# PHAS-Hub.net
KiCad netlist of a schematic drawn in EAGLE
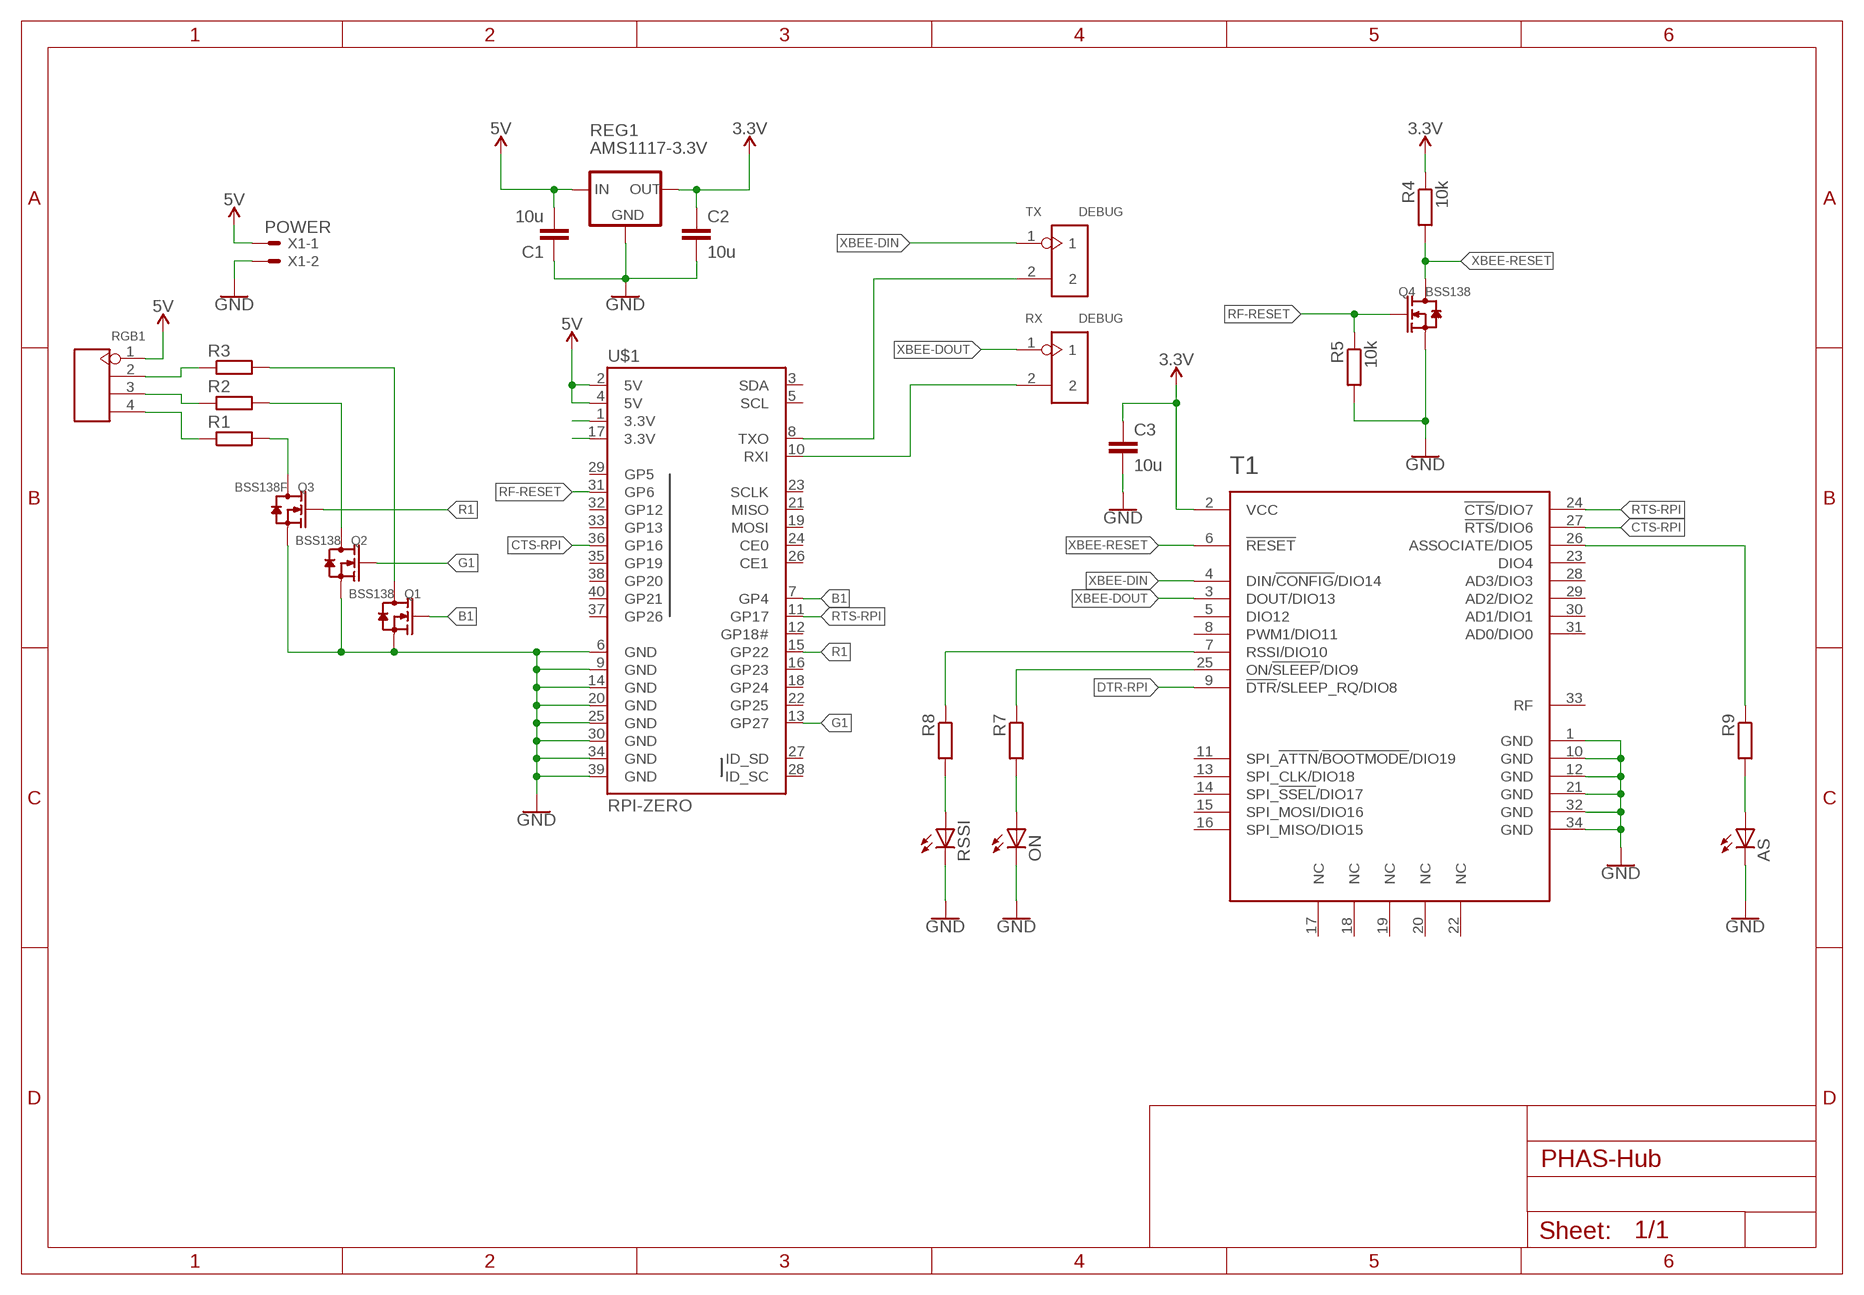
[diagram p0: schematic, sheet 1]

(export (version "E")
  (design (tool "Eeschema 10.0.6"))
  (components
    (comp (ref "AS")
      (value "LEDCHIPLED_0805")
      (footprint "eagle-import:CHIPLED_0805")
      (libsource (lib "eagle-import") (part "LEDCHIPLED_0805"))
    )
    (comp (ref "C1")
      (value "10u")
      (footprint "eagle-import:C0805")
      (libsource (lib "eagle-import") (part "C-EUC0805"))
    )
    (comp (ref "C2")
      (value "10u")
      (footprint "eagle-import:C0805")
      (libsource (lib "eagle-import") (part "C-EUC0805"))
    )
    (comp (ref "C3")
      (value "10u")
      (footprint "eagle-import:C0805")
      (libsource (lib "eagle-import") (part "C-EUC0805"))
    )
    (comp (ref "ON")
      (value "LEDCHIPLED_0805")
      (footprint "eagle-import:CHIPLED_0805")
      (libsource (lib "eagle-import") (part "LEDCHIPLED_0805"))
    )
    (comp (ref "Q1")
      (value "BSS138")
      (footprint "eagle-import:SOT-23")
      (fields (field (name "MPN") "BSS138W-7-F"))
      (libsource (lib "eagle-import") (part "SMD-MOSFET-N-CH-50V-200MA-BSS138W-7-F(SOT-23)"))
    )
    (comp (ref "Q2")
      (value "BSS138")
      (footprint "eagle-import:SOT-23")
      (fields (field (name "MPN") "BSS138W-7-F"))
      (libsource (lib "eagle-import") (part "SMD-MOSFET-N-CH-50V-200MA-BSS138W-7-F(SOT-23)"))
    )
    (comp (ref "Q3")
      (value "BSS138F")
      (footprint "eagle-import:SOT-23")
      (fields (field (name "MPN") "BSS138W-7-F"))
      (libsource (lib "eagle-import") (part "SMD-MOSFET-N-CH-50V-200MA-BSS138W-7-F(SOT-23)"))
    )
    (comp (ref "Q4")
      (value "BSS138")
      (footprint "eagle-import:SOT-23")
      (fields (field (name "MPN") "BSS138W-7-F"))
      (libsource (lib "eagle-import") (part "SMD-MOSFET-N-CH-50V-200MA-BSS138W-7-F(SOT-23)"))
    )
    (comp (ref "R1")
      (value "R-EU_R0805")
      (footprint "eagle-import:R0805")
      (libsource (lib "eagle-import") (part "R-EU_R0805"))
    )
    (comp (ref "R2")
      (value "R-EU_R0805")
      (footprint "eagle-import:R0805")
      (libsource (lib "eagle-import") (part "R-EU_R0805"))
    )
    (comp (ref "R3")
      (value "R-EU_R0805")
      (footprint "eagle-import:R0805")
      (libsource (lib "eagle-import") (part "R-EU_R0805"))
    )
    (comp (ref "R4")
      (value "10k")
      (footprint "eagle-import:R0805")
      (libsource (lib "eagle-import") (part "R-EU_R0805"))
    )
    (comp (ref "R5")
      (value "10k")
      (footprint "eagle-import:R0805")
      (libsource (lib "eagle-import") (part "R-EU_R0805"))
    )
    (comp (ref "R7")
      (value "R-EU_R0805")
      (footprint "eagle-import:R0805")
      (libsource (lib "eagle-import") (part "R-EU_R0805"))
    )
    (comp (ref "R8")
      (value "R-EU_R0805")
      (footprint "eagle-import:R0805")
      (libsource (lib "eagle-import") (part "R-EU_R0805"))
    )
    (comp (ref "R9")
      (value "R-EU_R0805")
      (footprint "eagle-import:R0805")
      (libsource (lib "eagle-import") (part "R-EU_R0805"))
    )
    (comp (ref "REG1")
      (value "AMS1117-3.3V")
      (footprint "eagle-import:SOT223")
      (fields (field (name "MF") "Texas Instruments") (field (name "MPN") "LM1117MP-3.3"))
      (libsource (lib "eagle-import") (part "LM1117?-MP3.3"))
    )
    (comp (ref "RGB1")
      (value "DIP-BLACK-MALE-HEADER-VERT(4P-2.54)")
      (footprint "eagle-import:H4-2.54")
      (fields (field (name "MPN") "P125-1104A0BS116A1"))
      (libsource (lib "eagle-import") (part "DIP-BLACK-MALE-HEADER-VERT(4P-2.54)"))
    )
    (comp (ref "RSSI")
      (value "LEDCHIPLED_0805")
      (footprint "eagle-import:CHIPLED_0805")
      (libsource (lib "eagle-import") (part "LEDCHIPLED_0805"))
    )
    (comp (ref "RX")
      (value "DEBUG")
      (footprint "eagle-import:H2-2.54")
      (fields (field (name "MPN") "P125-1102A0BS116A1"))
      (libsource (lib "eagle-import") (part "DIP-BLACK-MALE-HEADER-VERT(2P-2.54)"))
    )
    (comp (ref "T1")
      (value "XBEE3-MICRO")
      (footprint "eagle-import:XBEE3-MICRO")
      (libsource (lib "eagle-import") (part "XBEE3-MICRO"))
    )
    (comp (ref "TX")
      (value "DEBUG")
      (footprint "eagle-import:H2-2.54")
      (fields (field (name "MPN") "P125-1102A0BS116A1"))
      (libsource (lib "eagle-import") (part "DIP-BLACK-MALE-HEADER-VERT(2P-2.54)"))
    )
    (comp (ref "U$1")
      (value "RPI-ZERO")
      (footprint "eagle-import:RASPBERRYPI_BASTELSTUBE_V13_RASPI_BOARD_B+_FULL")
      (libsource (lib "eagle-import") (part "RPI-ZERO"))
    )
    (comp (ref "X1")
      (value "POWER")
      (footprint "eagle-import:70543-02")
      (fields (field (name "MF") "MOLEX"))
      (libsource (lib "eagle-import") (part "C-GRID-02-70543"))
    )
  )
  (nets
    (net (code "1") (name "3.3V") (class "Default")
      (node (ref "C2") (pin "1") (pinfunction "1_1") (pintype "passive"))
      (node (ref "C3") (pin "1") (pinfunction "1_1") (pintype "passive"))
      (node (ref "R4") (pin "1") (pinfunction "1_1") (pintype "passive"))
      (node (ref "REG1") (pin "2") (pinfunction "OUT_2") (pintype "passive"))
      (node (ref "REG1") (pin "4") (pinfunction "OUT_4") (pintype "passive"))
      (node (ref "T1") (pin "2") (pinfunction "VCC_2") (pintype "power_in"))
    )
    (net (code "2") (name "5V") (class "Default")
      (node (ref "C1") (pin "2") (pinfunction "2_2") (pintype "passive"))
      (node (ref "REG1") (pin "3") (pinfunction "IN_3") (pintype "input"))
      (node (ref "RGB1") (pin "1") (pinfunction "P$1_1") (pintype "bidirectional"))
      (node (ref "U$1") (pin "2") (pinfunction "5V_2") (pintype "power_in"))
      (node (ref "U$1") (pin "4") (pinfunction "5V_4") (pintype "power_in"))
      (node (ref "X1") (pin "1") (pinfunction "S_1") (pintype "passive"))
    )
    (net (code "3") (name "B1") (class "Default")
      (node (ref "Q1") (pin "1") (pinfunction "G_1") (pintype "passive"))
      (node (ref "U$1") (pin "7") (pinfunction "GP4_7") (pintype "bidirectional"))
    )
    (net (code "4") (name "CTS-RPI") (class "Default")
      (node (ref "T1") (pin "27") (pinfunction "~{RTS}/DIO6_27") (pintype "bidirectional"))
      (node (ref "U$1") (pin "36") (pinfunction "GP16_36") (pintype "bidirectional"))
    )
    (net (code "5") (name "DTR-RPI") (class "Default")
      (node (ref "T1") (pin "9") (pinfunction "~{DTR}/SLEEP_RQ/DIO8_9") (pintype "bidirectional"))
    )
    (net (code "6") (name "G1") (class "Default")
      (node (ref "Q2") (pin "1") (pinfunction "G_1") (pintype "passive"))
      (node (ref "U$1") (pin "13") (pinfunction "GP27_13") (pintype "bidirectional"))
    )
    (net (code "7") (name "GND") (class "Default")
      (node (ref "AS") (pin "C") (pinfunction "C_C") (pintype "passive"))
      (node (ref "C1") (pin "1") (pinfunction "1_1") (pintype "passive"))
      (node (ref "C2") (pin "2") (pinfunction "2_2") (pintype "passive"))
      (node (ref "C3") (pin "2") (pinfunction "2_2") (pintype "passive"))
      (node (ref "ON") (pin "C") (pinfunction "C_C") (pintype "passive"))
      (node (ref "Q1") (pin "2") (pinfunction "S_2") (pintype "passive"))
      (node (ref "Q2") (pin "2") (pinfunction "S_2") (pintype "passive"))
      (node (ref "Q3") (pin "2") (pinfunction "S_2") (pintype "passive"))
      (node (ref "Q4") (pin "2") (pinfunction "S_2") (pintype "passive"))
      (node (ref "R5") (pin "2") (pinfunction "2_2") (pintype "passive"))
      (node (ref "REG1") (pin "1") (pinfunction "GND_1") (pintype "input"))
      (node (ref "RSSI") (pin "C") (pinfunction "C_C") (pintype "passive"))
      (node (ref "T1") (pin "1") (pinfunction "GND_1") (pintype "power_in"))
      (node (ref "T1") (pin "10") (pinfunction "GND_10") (pintype "power_in"))
      (node (ref "T1") (pin "12") (pinfunction "GND_12") (pintype "power_in"))
      (node (ref "T1") (pin "21") (pinfunction "GND_21") (pintype "power_in"))
      (node (ref "T1") (pin "32") (pinfunction "GND_32") (pintype "power_in"))
      (node (ref "T1") (pin "34") (pinfunction "GND_34") (pintype "power_in"))
      (node (ref "U$1") (pin "14") (pinfunction "GND_14") (pintype "power_in"))
      (node (ref "U$1") (pin "20") (pinfunction "GND_20") (pintype "power_in"))
      (node (ref "U$1") (pin "25") (pinfunction "GND_25") (pintype "power_in"))
      (node (ref "U$1") (pin "30") (pinfunction "GND_30") (pintype "power_in"))
      (node (ref "U$1") (pin "34") (pinfunction "GND_34") (pintype "power_in"))
      (node (ref "U$1") (pin "39") (pinfunction "GND_39") (pintype "power_in"))
      (node (ref "U$1") (pin "6") (pinfunction "GND_6") (pintype "power_in"))
      (node (ref "U$1") (pin "9") (pinfunction "GND_9") (pintype "power_in"))
      (node (ref "X1") (pin "2") (pinfunction "S_2") (pintype "passive"))
    )
    (net (code "8") (name "Net-(AS-PadA)") (class "Default")
      (node (ref "AS") (pin "A") (pinfunction "A_A") (pintype "passive"))
      (node (ref "R9") (pin "2") (pinfunction "2_2") (pintype "passive"))
    )
    (net (code "9") (name "Net-(ON-PadA)") (class "Default")
      (node (ref "ON") (pin "A") (pinfunction "A_A") (pintype "passive"))
      (node (ref "R7") (pin "2") (pinfunction "2_2") (pintype "passive"))
    )
    (net (code "10") (name "Net-(Q1-D)") (class "Default")
      (node (ref "Q1") (pin "3") (pinfunction "D_3") (pintype "passive"))
      (node (ref "R3") (pin "2") (pinfunction "2_2") (pintype "passive"))
    )
    (net (code "11") (name "Net-(Q2-D)") (class "Default")
      (node (ref "Q2") (pin "3") (pinfunction "D_3") (pintype "passive"))
      (node (ref "R2") (pin "2") (pinfunction "2_2") (pintype "passive"))
    )
    (net (code "12") (name "Net-(Q3-D)") (class "Default")
      (node (ref "Q3") (pin "3") (pinfunction "D_3") (pintype "passive"))
      (node (ref "R1") (pin "2") (pinfunction "2_2") (pintype "passive"))
    )
    (net (code "13") (name "Net-(R8-Pad2)") (class "Default")
      (node (ref "R8") (pin "2") (pinfunction "2_2") (pintype "passive"))
      (node (ref "RSSI") (pin "A") (pinfunction "A_A") (pintype "passive"))
    )
    (net (code "14") (name "Net-(RGB1-P$2)") (class "Default")
      (node (ref "R3") (pin "1") (pinfunction "1_1") (pintype "passive"))
      (node (ref "RGB1") (pin "2") (pinfunction "P$2_2") (pintype "bidirectional"))
    )
    (net (code "15") (name "Net-(RGB1-P$3)") (class "Default")
      (node (ref "R2") (pin "1") (pinfunction "1_1") (pintype "passive"))
      (node (ref "RGB1") (pin "3") (pinfunction "P$3_3") (pintype "bidirectional"))
    )
    (net (code "16") (name "Net-(RGB1-P$4)") (class "Default")
      (node (ref "R1") (pin "1") (pinfunction "1_1") (pintype "passive"))
      (node (ref "RGB1") (pin "4") (pinfunction "P$4_4") (pintype "bidirectional"))
    )
    (net (code "17") (name "Net-(T1-ASSOCIATE{slash}DIO5)") (class "Default")
      (node (ref "R9") (pin "1") (pinfunction "1_1") (pintype "passive"))
      (node (ref "T1") (pin "26") (pinfunction "ASSOCIATE/DIO5_26") (pintype "bidirectional"))
    )
    (net (code "18") (name "Net-(T1-ON{slash}~{SLEEP}{slash}DIO9)") (class "Default")
      (node (ref "R7") (pin "1") (pinfunction "1_1") (pintype "passive"))
      (node (ref "T1") (pin "25") (pinfunction "ON/~{SLEEP}/DIO9_25") (pintype "bidirectional"))
    )
    (net (code "19") (name "Net-(T1-RSSI{slash}DIO10)") (class "Default")
      (node (ref "R8") (pin "1") (pinfunction "1_1") (pintype "passive"))
      (node (ref "T1") (pin "7") (pinfunction "RSSI/DIO10_7") (pintype "bidirectional"))
    )
    (net (code "20") (name "Net-(U$1-RXI)") (class "Default")
      (node (ref "RX") (pin "2") (pinfunction "2_2") (pintype "bidirectional"))
      (node (ref "U$1") (pin "10") (pinfunction "RXI_10") (pintype "input"))
    )
    (net (code "21") (name "Net-(U$1-TXO)") (class "Default")
      (node (ref "TX") (pin "2") (pinfunction "2_2") (pintype "bidirectional"))
      (node (ref "U$1") (pin "8") (pinfunction "TXO_8") (pintype "output"))
    )
    (net (code "22") (name "R1") (class "Default")
      (node (ref "Q3") (pin "1") (pinfunction "G_1") (pintype "passive"))
      (node (ref "U$1") (pin "15") (pinfunction "GP22_15") (pintype "bidirectional"))
    )
    (net (code "23") (name "RF-RESET") (class "Default")
      (node (ref "Q4") (pin "1") (pinfunction "G_1") (pintype "passive"))
      (node (ref "R5") (pin "1") (pinfunction "1_1") (pintype "passive"))
      (node (ref "U$1") (pin "31") (pinfunction "GP6_31") (pintype "bidirectional"))
    )
    (net (code "24") (name "RTS-RPI") (class "Default")
      (node (ref "T1") (pin "24") (pinfunction "~{CTS}/DIO7_24") (pintype "bidirectional"))
      (node (ref "U$1") (pin "11") (pinfunction "GP17_11") (pintype "bidirectional"))
    )
    (net (code "25") (name "XBEE-DIN") (class "Default")
      (node (ref "T1") (pin "4") (pinfunction "DIN/~{CONFIG}/DIO14_4") (pintype "bidirectional"))
      (node (ref "TX") (pin "1") (pinfunction "1_1") (pintype "bidirectional"))
    )
    (net (code "26") (name "XBEE-DOUT") (class "Default")
      (node (ref "RX") (pin "1") (pinfunction "1_1") (pintype "bidirectional"))
      (node (ref "T1") (pin "3") (pinfunction "DOUT/DIO13_3") (pintype "bidirectional"))
    )
    (net (code "27") (name "XBEE-RESET") (class "Default")
      (node (ref "Q4") (pin "3") (pinfunction "D_3") (pintype "passive"))
      (node (ref "R4") (pin "2") (pinfunction "2_2") (pintype "passive"))
      (node (ref "T1") (pin "6") (pinfunction "~{RESET}_6") (pintype "input"))
    )
    (net (code "28") (name "unconnected-(T1-AD0{slash}DIO0-Pad31)") (class "Default")
      (node (ref "T1") (pin "31") (pinfunction "AD0/DIO0_31") (pintype "bidirectional"))
    )
    (net (code "29") (name "unconnected-(T1-AD1{slash}DIO1-Pad30)") (class "Default")
      (node (ref "T1") (pin "30") (pinfunction "AD1/DIO1_30") (pintype "bidirectional"))
    )
    (net (code "30") (name "unconnected-(T1-AD2{slash}DIO2-Pad29)") (class "Default")
      (node (ref "T1") (pin "29") (pinfunction "AD2/DIO2_29") (pintype "bidirectional"))
    )
    (net (code "31") (name "unconnected-(T1-AD3{slash}DIO3-Pad28)") (class "Default")
      (node (ref "T1") (pin "28") (pinfunction "AD3/DIO3_28") (pintype "bidirectional"))
    )
    (net (code "32") (name "unconnected-(T1-DIO4-Pad23)") (class "Default")
      (node (ref "T1") (pin "23") (pinfunction "DIO4_23") (pintype "bidirectional"))
    )
    (net (code "33") (name "unconnected-(T1-DIO12-Pad5)") (class "Default")
      (node (ref "T1") (pin "5") (pinfunction "DIO12_5") (pintype "bidirectional"))
    )
    (net (code "34") (name "unconnected-(T1-NC-Pad17)") (class "Default")
      (node (ref "T1") (pin "17") (pinfunction "NC_17") (pintype "bidirectional"))
    )
    (net (code "35") (name "unconnected-(T1-NC-Pad18)") (class "Default")
      (node (ref "T1") (pin "18") (pinfunction "NC_18") (pintype "bidirectional"))
    )
    (net (code "36") (name "unconnected-(T1-NC-Pad19)") (class "Default")
      (node (ref "T1") (pin "19") (pinfunction "NC_19") (pintype "bidirectional"))
    )
    (net (code "37") (name "unconnected-(T1-NC-Pad20)") (class "Default")
      (node (ref "T1") (pin "20") (pinfunction "NC_20") (pintype "bidirectional"))
    )
    (net (code "38") (name "unconnected-(T1-NC-Pad22)") (class "Default")
      (node (ref "T1") (pin "22") (pinfunction "NC_22") (pintype "bidirectional"))
    )
    (net (code "39") (name "unconnected-(T1-PWM1{slash}DIO11-Pad8)") (class "Default")
      (node (ref "T1") (pin "8") (pinfunction "PWM1/DIO11_8") (pintype "bidirectional"))
    )
    (net (code "40") (name "unconnected-(T1-RF-Pad33)") (class "Default")
      (node (ref "T1") (pin "33") (pinfunction "RF_33") (pintype "output"))
    )
    (net (code "41") (name "unconnected-(T1-SPI_CLK{slash}DIO18-Pad13)") (class "Default")
      (node (ref "T1") (pin "13") (pinfunction "SPI_CLK/DIO18_13") (pintype "bidirectional"))
    )
    (net (code "42") (name "unconnected-(T1-SPI_MISO{slash}DIO15-Pad16)") (class "Default")
      (node (ref "T1") (pin "16") (pinfunction "SPI_MISO/DIO15_16") (pintype "bidirectional"))
    )
    (net (code "43") (name "unconnected-(T1-SPI_MOSI{slash}DIO16-Pad15)") (class "Default")
      (node (ref "T1") (pin "15") (pinfunction "SPI_MOSI/DIO16_15") (pintype "bidirectional"))
    )
    (net (code "44") (name "unconnected-(T1-SPI_~{ATTN}{slash}~{BOOTMODE}{slash}DIO19-Pad11)") (class "Default")
      (node (ref "T1") (pin "11") (pinfunction "SPI_~{ATTN}/~{BOOTMODE}/DIO19_11") (pintype "bidirectional"))
    )
    (net (code "45") (name "unconnected-(T1-SPI_~{SSEL}{slash}DIO17-Pad14)") (class "Default")
      (node (ref "T1") (pin "14") (pinfunction "SPI_~{SSEL}/DIO17_14") (pintype "bidirectional"))
    )
    (net (code "46") (name "unconnected-(U$1-3.3V-Pad1)") (class "Default")
      (node (ref "U$1") (pin "1") (pinfunction "3.3V_1") (pintype "power_in"))
    )
    (net (code "47") (name "unconnected-(U$1-3.3V-Pad17)") (class "Default")
      (node (ref "U$1") (pin "17") (pinfunction "3.3V_17") (pintype "power_in"))
    )
    (net (code "48") (name "unconnected-(U$1-CE0-Pad24)") (class "Default")
      (node (ref "U$1") (pin "24") (pinfunction "CE0_24") (pintype "output"))
    )
    (net (code "49") (name "unconnected-(U$1-CE1-Pad26)") (class "Default")
      (node (ref "U$1") (pin "26") (pinfunction "CE1_26") (pintype "output"))
    )
    (net (code "50") (name "unconnected-(U$1-GP5-Pad29)") (class "Default")
      (node (ref "U$1") (pin "29") (pinfunction "GP5_29") (pintype "bidirectional"))
    )
    (net (code "51") (name "unconnected-(U$1-GP12-Pad32)") (class "Default")
      (node (ref "U$1") (pin "32") (pinfunction "GP12_32") (pintype "bidirectional"))
    )
    (net (code "52") (name "unconnected-(U$1-GP13-Pad33)") (class "Default")
      (node (ref "U$1") (pin "33") (pinfunction "GP13_33") (pintype "bidirectional"))
    )
    (net (code "53") (name "unconnected-(U$1-GP18#-Pad12)") (class "Default")
      (node (ref "U$1") (pin "12") (pinfunction "GP18#_12") (pintype "bidirectional"))
    )
    (net (code "54") (name "unconnected-(U$1-GP19-Pad35)") (class "Default")
      (node (ref "U$1") (pin "35") (pinfunction "GP19_35") (pintype "bidirectional"))
    )
    (net (code "55") (name "unconnected-(U$1-GP20-Pad38)") (class "Default")
      (node (ref "U$1") (pin "38") (pinfunction "GP20_38") (pintype "bidirectional"))
    )
    (net (code "56") (name "unconnected-(U$1-GP21-Pad40)") (class "Default")
      (node (ref "U$1") (pin "40") (pinfunction "GP21_40") (pintype "bidirectional"))
    )
    (net (code "57") (name "unconnected-(U$1-GP23-Pad16)") (class "Default")
      (node (ref "U$1") (pin "16") (pinfunction "GP23_16") (pintype "bidirectional"))
    )
    (net (code "58") (name "unconnected-(U$1-GP24-Pad18)") (class "Default")
      (node (ref "U$1") (pin "18") (pinfunction "GP24_18") (pintype "bidirectional"))
    )
    (net (code "59") (name "unconnected-(U$1-GP25-Pad22)") (class "Default")
      (node (ref "U$1") (pin "22") (pinfunction "GP25_22") (pintype "bidirectional"))
    )
    (net (code "60") (name "unconnected-(U$1-GP26-Pad37)") (class "Default")
      (node (ref "U$1") (pin "37") (pinfunction "GP26_37") (pintype "bidirectional"))
    )
    (net (code "61") (name "unconnected-(U$1-ID_SC-Pad28)") (class "Default")
      (node (ref "U$1") (pin "28") (pinfunction "ID_SC_28") (pintype "bidirectional"))
    )
    (net (code "62") (name "unconnected-(U$1-ID_SD-Pad27)") (class "Default")
      (node (ref "U$1") (pin "27") (pinfunction "ID_SD_27") (pintype "bidirectional"))
    )
    (net (code "63") (name "unconnected-(U$1-MISO-Pad21)") (class "Default")
      (node (ref "U$1") (pin "21") (pinfunction "MISO_21") (pintype "input"))
    )
    (net (code "64") (name "unconnected-(U$1-MOSI-Pad19)") (class "Default")
      (node (ref "U$1") (pin "19") (pinfunction "MOSI_19") (pintype "output"))
    )
    (net (code "65") (name "unconnected-(U$1-SCL-Pad5)") (class "Default")
      (node (ref "U$1") (pin "5") (pinfunction "SCL_5") (pintype "bidirectional"))
    )
    (net (code "66") (name "unconnected-(U$1-SCLK-Pad23)") (class "Default")
      (node (ref "U$1") (pin "23") (pinfunction "SCLK_23") (pintype "output"))
    )
    (net (code "67") (name "unconnected-(U$1-SDA-Pad3)") (class "Default")
      (node (ref "U$1") (pin "3") (pinfunction "SDA_3") (pintype "bidirectional"))
    )
  )
)
